# JacdacTempRhEc30_116.net
KiCad netlist of a schematic drawn in Altium Designer
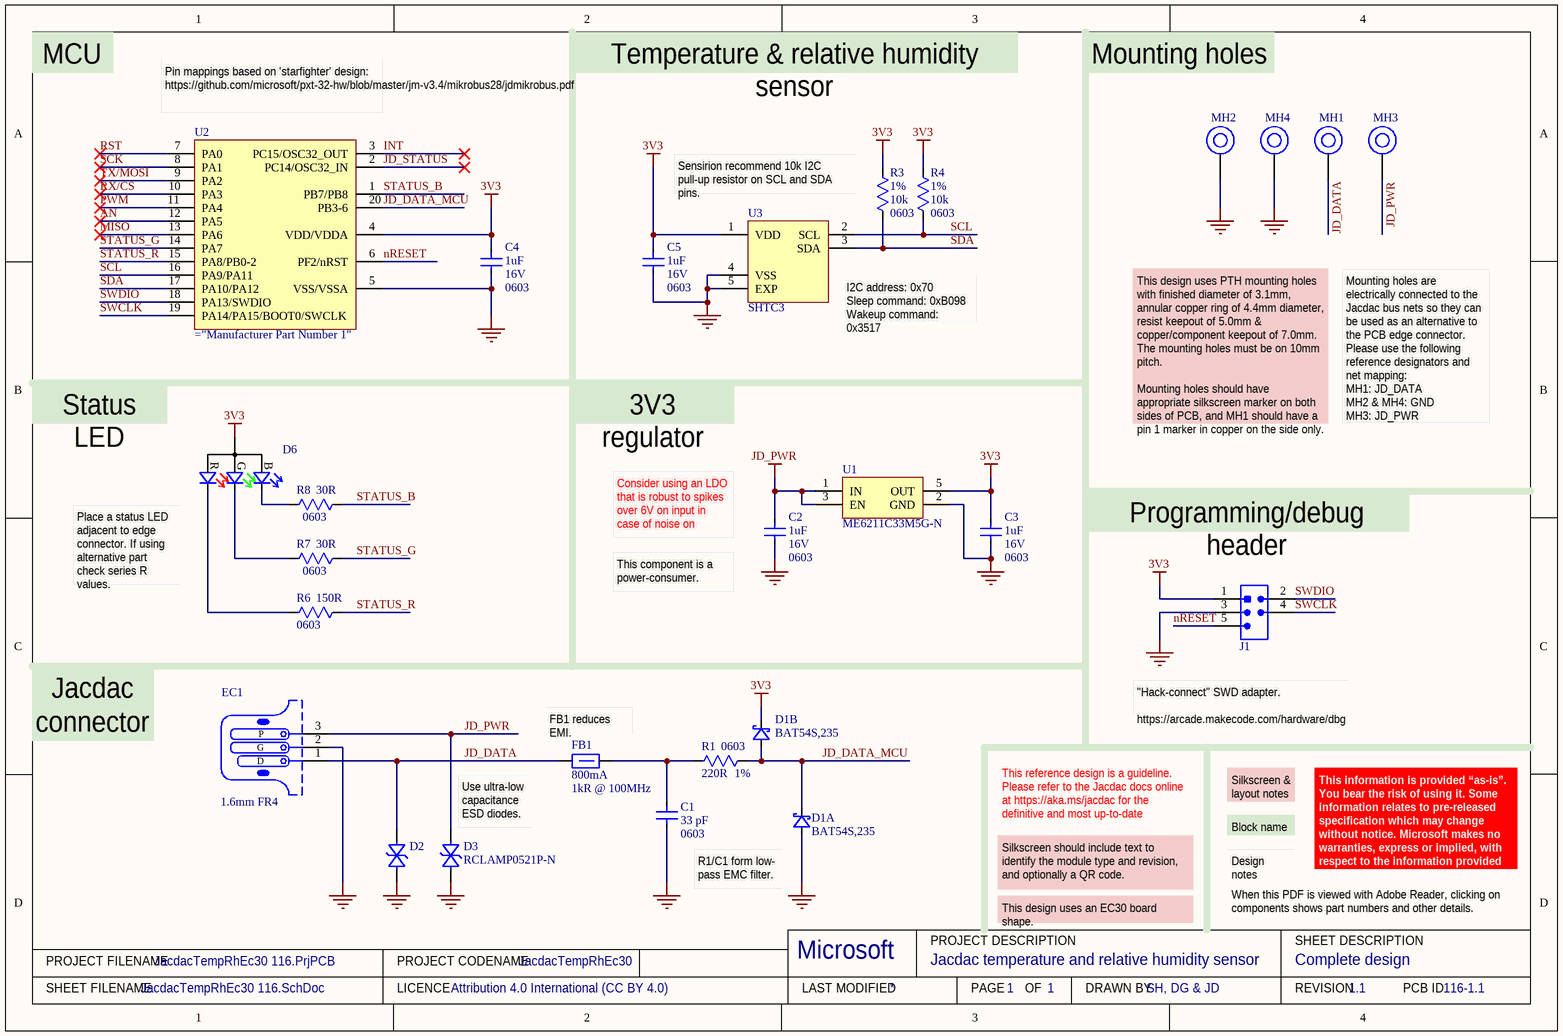
[diagram p0: JacdacTempRhEc30 116.SchDoc]

(export (version "E")
  (design (tool "Eeschema 10.0.6"))
  (components
    (comp (ref "C1")
      (value "33 pF")
      (footprint "YAGEO-0603:CC0603")
      (description "33pF 0603 100V C0G/NPO")
      (fields
        (field (name "MANUFACTURER") "Yageo")
        (field (name "MANUFACTURER PART NUMBER") "CC0603JRNPO9BN330")
        (field (name "CASE/PACKAGE") "0603")
      )
      (libsource (lib "Yageo") (part "CC0603JRNPO9BN330"))
    )
    (comp (ref "C2")
      (value "1uF 16V")
      (footprint "SAMSUNG-CAP-0603:C0603 - without outline")
      (description "SMD Multilayer Ceramic Capacitor, 1 µF, 16 V, 0603 [1608 Metric], ± 10%, X5R, CL Series")
      (fields
        (field (name "MANUFACTURER") "Samsung")
        (field (name "MANUFACTURER PART NUMBER") "CL10A105KO8NNNC")
        (field (name "VOLTAGE") "16V")
        (field (name "CASE/PACKAGE") "0603")
        (field (name "CAPACITANCE") "1uF")
      )
      (libsource (lib "Samsung") (part "CL10A105KO8NNNC"))
    )
    (comp (ref "C3")
      (value "1uF 16V")
      (footprint "SAMSUNG-CAP-0603:C0603 - without outline")
      (description "SMD Multilayer Ceramic Capacitor, 1 µF, 16 V, 0603 [1608 Metric], ± 10%, X5R, CL Series")
      (fields
        (field (name "MANUFACTURER") "Samsung")
        (field (name "MANUFACTURER PART NUMBER") "CL10A105KO8NNNC")
        (field (name "VOLTAGE") "16V")
        (field (name "CASE/PACKAGE") "0603")
        (field (name "CAPACITANCE") "1uF")
      )
      (libsource (lib "Samsung") (part "CL10A105KO8NNNC"))
    )
    (comp (ref "C4")
      (value "1uF 16V")
      (footprint "SAMSUNG-CAP-0603:C0603 - without outline")
      (description "SMD Multilayer Ceramic Capacitor, 1 µF, 16 V, 0603 [1608 Metric], ± 10%, X5R, CL Series")
      (fields
        (field (name "MANUFACTURER") "Samsung")
        (field (name "MANUFACTURER PART NUMBER") "CL10A105KO8NNNC")
        (field (name "VOLTAGE") "16V")
        (field (name "CASE/PACKAGE") "0603")
        (field (name "CAPACITANCE") "1uF")
      )
      (libsource (lib "Samsung") (part "CL10A105KO8NNNC"))
    )
    (comp (ref "C5")
      (value "1uF 16V")
      (footprint "SAMSUNG-CAP-0603:C0603 - without outline")
      (description "SMD Multilayer Ceramic Capacitor, 1 µF, 16 V, 0603 [1608 Metric], ± 10%, X5R, CL Series")
      (fields
        (field (name "MANUFACTURER") "Samsung")
        (field (name "MANUFACTURER PART NUMBER") "CL10A105KO8NNNC")
        (field (name "VOLTAGE") "16V")
        (field (name "CASE/PACKAGE") "0603")
        (field (name "CAPACITANCE") "1uF")
      )
      (libsource (lib "Samsung") (part "CL10A105KO8NNNC"))
    )
    (comp (ref "D1")
      (value "BAT54S")
      (footprint "NXP-BAT54S-TO-236AB - without outline")
      (description "DIODE ARRAY SCHOTTKY 30V SOT23")
      (fields (field (name "MANUFACTURER") "Nexperia") (field (name "MANUFACTURER PART NUMBER") "BAT54S,235"))
      (libsource (lib "NXP") (part "BAT54S"))
    )
    (comp (ref "D2")
      (value "RCLAMP0521P-N")
      (footprint "0402:TVS 0402 - XL")
      (description "Bidirectional 5V (Max) 6V 16V 3.5A (8/20us) 0402 TVS RoHS")
      (fields
        (field (name "MANUFACTURER") "Born Semiconductor")
        (field (name "CREATED BY") "D Gakure")
        (field (name "CHECKED BY") "?")
      )
      (libsource (lib "BornSemiconductor") (part "RCLAMP0521P-N"))
    )
    (comp (ref "D3")
      (value "RCLAMP0521P-N")
      (footprint "0402:TVS 0402 - XL")
      (description "Bidirectional 5V (Max) 6V 16V 3.5A (8/20us) 0402 TVS RoHS")
      (fields
        (field (name "MANUFACTURER") "Born Semiconductor")
        (field (name "MANUFACTURER PART NUMBER") "RCLAMP0521P-N")
        (field (name "CREATED BY") "D Gakure")
        (field (name "CHECKED BY") "?")
      )
      (libsource (lib "BornSemiconductor") (part "RCLAMP0521P-N"))
    )
    (comp (ref "D6")
      (value "TZ-P4-1615RGBTCA1-0.55T")
      (footprint "TZ-P4-1615RGBTCA1-0.55T")
      (description "1615 Light Emitting Diodes (LED) RoHS")
      (fields
        (field (name "MANUFACTURER") "TUOZHAN")
        (field (name "CREATED BY") "D. Gakure")
        (field (name "CHECKED BY") "?")
      )
      (libsource (lib "Tuozhan") (part "TZ-P4-1615RGBTCA1-0.55T"))
    )
    (comp (ref "EC1")
      (value "3 pin JACDAC edge connector")
      (footprint "JACDAC_edge_connector:JACDAC_EDGE_CONNECTOR_NO_TRACES")
      (description "3 pin Jacdac edge connector 1.27mm pitch")
      (fields
        (field (name "MANUFACTURER PART NUMBER") "JACDAC_EDGE_CONNECTOR")
        (field (name "PCB TYPE") "1.6mm FR4")
        (field (name "CHECKED BY") "?")
        (field (name "CREATED BY") "D. Gakure")
      )
      (libsource (lib "generic-con") (part "Jacdac edge connector"))
    )
    (comp (ref "FB1")
      (value "TDK MPZ1608S102ATA00")
      (footprint "TDK MPZ1608 0.8mm - without outline")
      (description "0603 1k@100MHz 0.8A chip")
      (fields
        (field (name "TOLERANCE") "25%")
        (field (name "MANUFACTURER") "TDK")
        (field (name "CURRENT RATING") "800mA")
        (field (name "IMPEDANCE") "1kR @ 100MHz")
      )
      (libsource (lib "TDK") (part "TDK MPZ1608S102ATA00"))
    )
    (comp (ref "J1")
      (value "Hack Connect Mini 1.27 mm pitch 2-row")
      (footprint "HackConnect:HACK_CONNECT_MINI_5_X_1_27")
      (libsource (lib "generic-con") (part "HACK_CONNECT_MINI"))
    )
    (comp (ref "MH1")
      (value "MH_7.0MMK_4.4MMC_3.1MMD_PTH")
      (footprint "MH_7.0MMK_4.4MMC_3.1MMD_PTH:MH_7.0MMK_4.4MMC_3.1MMD_PTH")
      (description "Mounting Hole 7.0mm keepout, 4.4mm annualar ring and 3.1mm Drill PTH")
      (libsource (lib "generic") (part "MH_7.0MMK_4.4MMC_3.1MMD_PTH"))
    )
    (comp (ref "MH2")
      (value "MH_7.0MMK_4.4MMC_3.1MMD_PTH")
      (footprint "MH_7.0MMK_4.4MMC_3.1MMD_PTH:MH_7.0MMK_4.4MMC_3.1MMD_PTH")
      (description "Mounting Hole 7.0mm keepout, 4.4mm annualar ring and 3.1mm Drill PTH")
      (libsource (lib "generic") (part "MH_7.0MMK_4.4MMC_3.1MMD_PTH"))
    )
    (comp (ref "MH3")
      (value "MH_7.0MMK_4.4MMC_3.1MMD_PTH")
      (footprint "MH_7.0MMK_4.4MMC_3.1MMD_PTH:MH_7.0MMK_4.4MMC_3.1MMD_PTH")
      (description "Mounting Hole 7.0mm keepout, 4.4mm annualar ring and 3.1mm Drill PTH")
      (libsource (lib "generic") (part "MH_7.0MMK_4.4MMC_3.1MMD_PTH"))
    )
    (comp (ref "MH4")
      (value "MH_7.0MMK_4.4MMC_3.1MMD_PTH")
      (footprint "MH_7.0MMK_4.4MMC_3.1MMD_PTH:MH_7.0MMK_4.4MMC_3.1MMD_PTH")
      (description "Mounting Hole 7.0mm keepout, 4.4mm annualar ring and 3.1mm Drill PTH")
      (libsource (lib "generic") (part "MH_7.0MMK_4.4MMC_3.1MMD_PTH"))
    )
    (comp (ref "R1")
      (value "220R")
      (footprint "YAGEO-0603:RC0603")
      (description "Res Thick Film 0603 220 Ohm 1% 0.1W(1/10W) ±100ppm/°C Pad SMD T/R")
      (fields
        (field (name "MANUFACTURER") "Yageo")
        (field (name "MANUFACTURER PART NUMBER") "RC0603FR-07220RL")
        (field (name "TOLERANCE") "1%")
        (field (name "RESISTANCE") "220R")
        (field (name "CASE/PACKAGE") "0603")
      )
      (libsource (lib "Yageo") (part "RC0603FR-07220RL"))
    )
    (comp (ref "R3")
      (value "10k")
      (footprint "YAGEO-0603:RC0603")
      (description "Res Thick Film 0603 10k ohm 1% 0.1W(1/10W) ±100ppm/°C Pad SMD T/R")
      (fields
        (field (name "MANUFACTURER") "Yageo")
        (field (name "MANUFACTURER PART NUMBER") "RC0603FR-0710KL")
        (field (name "TOLERANCE") "1%")
        (field (name "RESISTANCE") "10k")
        (field (name "CASE/PACKAGE") "0603")
      )
      (libsource (lib "Yageo") (part "RC0603FR-07220RL"))
    )
    (comp (ref "R4")
      (value "10k")
      (footprint "YAGEO-0603:RC0603")
      (description "Res Thick Film 0603 10k ohm 1% 0.1W(1/10W) ±100ppm/°C Pad SMD T/R")
      (fields
        (field (name "MANUFACTURER") "Yageo")
        (field (name "MANUFACTURER PART NUMBER") "RC0603FR-0710KL")
        (field (name "TOLERANCE") "1%")
        (field (name "RESISTANCE") "10k")
        (field (name "CASE/PACKAGE") "0603")
      )
      (libsource (lib "Yageo") (part "RC0603FR-07220RL"))
    )
    (comp (ref "R6")
      (value "150R")
      (footprint "YAGEO-0603:RC0603")
      (description "Res General Purpose Thick Film 0603 150 Ohm 1% 1/10W ±100ppm/°C Molded SMD Paper T/R")
      (fields
        (field (name "MANUFACTURER") "Yageo")
        (field (name "MANUFACTURER PART NUMBER") "RC0603FR-07150RL")
        (field (name "CASE/PACKAGE") "0603")
        (field (name "RESISTANCE") "150R")
      )
      (libsource (lib "Yageo") (part "RC0603FR-07150RL"))
    )
    (comp (ref "R7")
      (value "30R")
      (footprint "YAGEO-0603:RC0603")
      (description "Res Thick Film 0603 30 Ohm 1% 0.1W(1/10W) ±100ppm/C Pad SMD T/R")
      (fields
        (field (name "MANUFACTURER") "Yageo")
        (field (name "MANUFACTURER PART NUMBER") "RC0603FR-0730RL")
        (field (name "RESISTANCE") "30R")
        (field (name "CASE/PACKAGE") "0603")
      )
      (libsource (lib "Yageo") (part "RC0603FR-0730RL"))
    )
    (comp (ref "R8")
      (value "30R")
      (footprint "YAGEO-0603:RC0603")
      (description "Res Thick Film 0603 30 Ohm 1% 0.1W(1/10W) ±100ppm/C Pad SMD T/R")
      (fields
        (field (name "MANUFACTURER") "Yageo")
        (field (name "MANUFACTURER PART NUMBER") "RC0603FR-0730RL")
        (field (name "RESISTANCE") "30R")
        (field (name "CASE/PACKAGE") "0603")
      )
      (libsource (lib "Yageo") (part "RC0603FR-0730RL"))
    )
    (comp (ref "U1")
      (value "ME6211C33M5G-N")
      (footprint "MICRONE-SOT23-5:MICRONE-SOT23-5")
      (description "6V 260mV @ 200mA(typ) - - Fixed 3.3V SOT-23-5 Linear Voltage Regulators (LDO) ROHS")
      (fields
        (field (name "MANUFACTURER") "MICRONE(Nanjing Micro One Elec)")
        (field (name "MANUFACTURER PART NUMBER") "ME6211C33M5G-N")
        (field (name "CREATED") "DG")
      )
      (libsource (lib "MICRONE(NanjingMicroOneElec)") (part "ME6211C33M5G-N"))
    )
    (comp (ref "U2")
      (value "~")
      (footprint "ST-STM32F030F4P6:20-TSSOP")
      (description "ARM® Cortex®-M0+ series IC 64MHz 32KB 20-TSSOP")
      (fields
        (field (name "MANUFACTURER") "STMicroelectronics")
        (field (name "MANUFACTURER PART NUMBER") "STM32G030F6P6")
      )
      (libsource (lib "ST") (part "STM32G030F6P6"))
    )
    (comp (ref "U3")
      (value "SHTC3")
      (footprint "SENSIRION_SHTC3:SHTC3_4_WDFN")
      (description "Humidity Temperature Sensor 0 ~ 100% RH I²C ±2% RH 8s Surface Mount")
      (fields
        (field (name "MANUFACTURER") "Sensirion")
        (field (name "MANUFACTURER PART NUMBER") "SHTC3")
        (field (name "CREATED BY") "D. Gakure")
        (field (name "CHECKED BY") "?")
      )
      (libsource (lib "Sensirion") (part "SHTC3"))
    )
  )
  (nets
    (net (code "1") (name "/AN") (class "Default")
      (node (ref "U2") (pin "12") (pinfunction "PA5_12") (pintype "passive+no_connect"))
    )
    (net (code "2") (name "/INT") (class "Default")
      (node (ref "U2") (pin "3") (pinfunction "PC15/OSC32_OUT_3") (pintype "passive+no_connect"))
    )
    (net (code "3") (name "/JD_DATA") (class "Default")
      (node (ref "D2") (pin "1") (pinfunction "K_1") (pintype "passive"))
      (node (ref "EC1") (pin "1") (pinfunction "D_1") (pintype "passive"))
      (node (ref "FB1") (pin "1") (pinfunction "1_1") (pintype "passive"))
      (node (ref "MH1") (pin "1") (pinfunction "1_1") (pintype "passive"))
    )
    (net (code "4") (name "/JD_DATA_MCU") (class "Default")
      (node (ref "D1") (pin "3") (pinfunction "K_3") (pintype "passive"))
      (node (ref "R1") (pin "2") (pinfunction "2_2") (pintype "passive"))
      (node (ref "U2") (pin "20") (pinfunction "PB3-6_20") (pintype "power_in"))
    )
    (net (code "5") (name "/JD_STATUS") (class "Default")
      (node (ref "U2") (pin "2") (pinfunction "PC14/OSC32_IN_2") (pintype "passive+no_connect"))
    )
    (net (code "6") (name "/MISO") (class "Default")
      (node (ref "U2") (pin "13") (pinfunction "PA6_13") (pintype "passive+no_connect"))
    )
    (net (code "7") (name "/PWM") (class "Default")
      (node (ref "U2") (pin "11") (pinfunction "PA4_11") (pintype "passive+no_connect"))
    )
    (net (code "8") (name "/RST") (class "Default")
      (node (ref "U2") (pin "7") (pinfunction "PA0_7") (pintype "passive+no_connect"))
    )
    (net (code "9") (name "/RX{slash}CS") (class "Default")
      (node (ref "U2") (pin "10") (pinfunction "PA3_10") (pintype "passive+no_connect"))
    )
    (net (code "10") (name "/SCK") (class "Default")
      (node (ref "U2") (pin "8") (pinfunction "PA1_8") (pintype "passive+no_connect"))
    )
    (net (code "11") (name "/SCL") (class "Default")
      (node (ref "R4") (pin "2") (pinfunction "2_2") (pintype "passive"))
      (node (ref "U2") (pin "16") (pinfunction "PA9/PA11_16") (pintype "passive"))
      (node (ref "U3") (pin "2") (pinfunction "SCL_2") (pintype "passive"))
    )
    (net (code "12") (name "/SDA") (class "Default")
      (node (ref "R3") (pin "2") (pinfunction "2_2") (pintype "passive"))
      (node (ref "U2") (pin "17") (pinfunction "PA10/PA12_17") (pintype "passive"))
      (node (ref "U3") (pin "3") (pinfunction "SDA_3") (pintype "passive"))
    )
    (net (code "13") (name "/STATUS_B") (class "Default")
      (node (ref "R8") (pin "2") (pinfunction "2_2") (pintype "passive"))
      (node (ref "U2") (pin "1") (pinfunction "PB7/PB8_1") (pintype "passive"))
    )
    (net (code "14") (name "/STATUS_G") (class "Default")
      (node (ref "R7") (pin "2") (pinfunction "2_2") (pintype "passive"))
      (node (ref "U2") (pin "14") (pinfunction "PA7_14") (pintype "passive"))
    )
    (net (code "15") (name "/STATUS_R") (class "Default")
      (node (ref "R6") (pin "2") (pinfunction "2_2") (pintype "passive"))
      (node (ref "U2") (pin "15") (pinfunction "PA8/PB0-2_15") (pintype "passive"))
    )
    (net (code "16") (name "/SWCLK") (class "Default")
      (node (ref "J1") (pin "4") (pinfunction "SWCLK_4") (pintype "passive"))
      (node (ref "U2") (pin "19") (pinfunction "PA14/PA15/BOOT0/SWCLK_19") (pintype "passive"))
    )
    (net (code "17") (name "/SWDIO") (class "Default")
      (node (ref "J1") (pin "2") (pinfunction "SWDIO_2") (pintype "passive"))
      (node (ref "U2") (pin "18") (pinfunction "PA13/SWDIO_18") (pintype "passive"))
    )
    (net (code "18") (name "/TX{slash}MOSI") (class "Default")
      (node (ref "U2") (pin "9") (pinfunction "PA2_9") (pintype "passive+no_connect"))
    )
    (net (code "19") (name "/nRESET") (class "Default")
      (node (ref "J1") (pin "5") (pinfunction "RESET_5") (pintype "passive"))
      (node (ref "U2") (pin "6") (pinfunction "PF2/nRST_6") (pintype "power_in"))
    )
    (net (code "20") (name "3V3") (class "Default")
      (node (ref "C3") (pin "2") (pinfunction "2_2") (pintype "passive"))
      (node (ref "C4") (pin "2") (pinfunction "2_2") (pintype "passive"))
      (node (ref "C5") (pin "2") (pinfunction "2_2") (pintype "passive"))
      (node (ref "D1") (pin "2") (pinfunction "K_2") (pintype "passive"))
      (node (ref "D6") (pin "1") (pinfunction "A_1") (pintype "passive"))
      (node (ref "J1") (pin "1") (pinfunction "VCC_1") (pintype "passive"))
      (node (ref "R3") (pin "1") (pinfunction "1_1") (pintype "passive"))
      (node (ref "R4") (pin "1") (pinfunction "1_1") (pintype "passive"))
      (node (ref "U1") (pin "5") (pinfunction "OUT_5") (pintype "passive"))
      (node (ref "U2") (pin "4") (pinfunction "VDD/VDDA_4") (pintype "passive"))
      (node (ref "U3") (pin "1") (pinfunction "VDD_1") (pintype "passive"))
    )
    (net (code "21") (name "GND") (class "Default")
      (node (ref "C1") (pin "1") (pinfunction "1_1") (pintype "passive"))
      (node (ref "C2") (pin "1") (pinfunction "1_1") (pintype "passive"))
      (node (ref "C3") (pin "1") (pinfunction "1_1") (pintype "passive"))
      (node (ref "C4") (pin "1") (pinfunction "1_1") (pintype "passive"))
      (node (ref "C5") (pin "1") (pinfunction "1_1") (pintype "passive"))
      (node (ref "D1") (pin "1") (pinfunction "A_1") (pintype "passive"))
      (node (ref "D2") (pin "2") (pinfunction "A_2") (pintype "passive"))
      (node (ref "D3") (pin "2") (pinfunction "A_2") (pintype "passive"))
      (node (ref "EC1") (pin "2") (pinfunction "G_2") (pintype "passive"))
      (node (ref "J1") (pin "3") (pinfunction "GND_3") (pintype "passive"))
      (node (ref "MH2") (pin "1") (pinfunction "1_1") (pintype "passive"))
      (node (ref "MH4") (pin "1") (pinfunction "1_1") (pintype "passive"))
      (node (ref "U1") (pin "2") (pinfunction "GND_2") (pintype "passive"))
      (node (ref "U2") (pin "5") (pinfunction "VSS/VSSA_5") (pintype "power_in"))
      (node (ref "U3") (pin "4") (pinfunction "VSS_4") (pintype "passive"))
      (node (ref "U3") (pin "5") (pinfunction "EXP_5") (pintype "passive"))
    )
    (net (code "22") (name "JD_PWR") (class "Default")
      (node (ref "C2") (pin "2") (pinfunction "2_2") (pintype "passive"))
      (node (ref "D3") (pin "1") (pinfunction "K_1") (pintype "passive"))
      (node (ref "EC1") (pin "3") (pinfunction "P_3") (pintype "passive"))
      (node (ref "MH3") (pin "1") (pinfunction "1_1") (pintype "passive"))
      (node (ref "U1") (pin "1") (pinfunction "IN_1") (pintype "passive"))
      (node (ref "U1") (pin "3") (pinfunction "EN_3") (pintype "passive"))
    )
    (net (code "23") (name "Net-(C1-Pad2)") (class "Default")
      (node (ref "C1") (pin "2") (pinfunction "2_2") (pintype "passive"))
      (node (ref "FB1") (pin "2") (pinfunction "2_2") (pintype "passive"))
      (node (ref "R1") (pin "1") (pinfunction "1_1") (pintype "passive"))
    )
    (net (code "24") (name "Net-(D6-B)") (class "Default")
      (node (ref "D6") (pin "4") (pinfunction "B_4") (pintype "passive"))
      (node (ref "R8") (pin "1") (pinfunction "1_1") (pintype "passive"))
    )
    (net (code "25") (name "Net-(D6-G)") (class "Default")
      (node (ref "D6") (pin "3") (pinfunction "G_3") (pintype "passive"))
      (node (ref "R7") (pin "1") (pinfunction "1_1") (pintype "passive"))
    )
    (net (code "26") (name "Net-(D6-R)") (class "Default")
      (node (ref "D6") (pin "2") (pinfunction "R_2") (pintype "passive"))
      (node (ref "R6") (pin "1") (pinfunction "1_1") (pintype "passive"))
    )
  )
)
